# RBB_MCU7_V2_2_Connector.net
KiCad netlist of a schematic drawn in Altium Designer
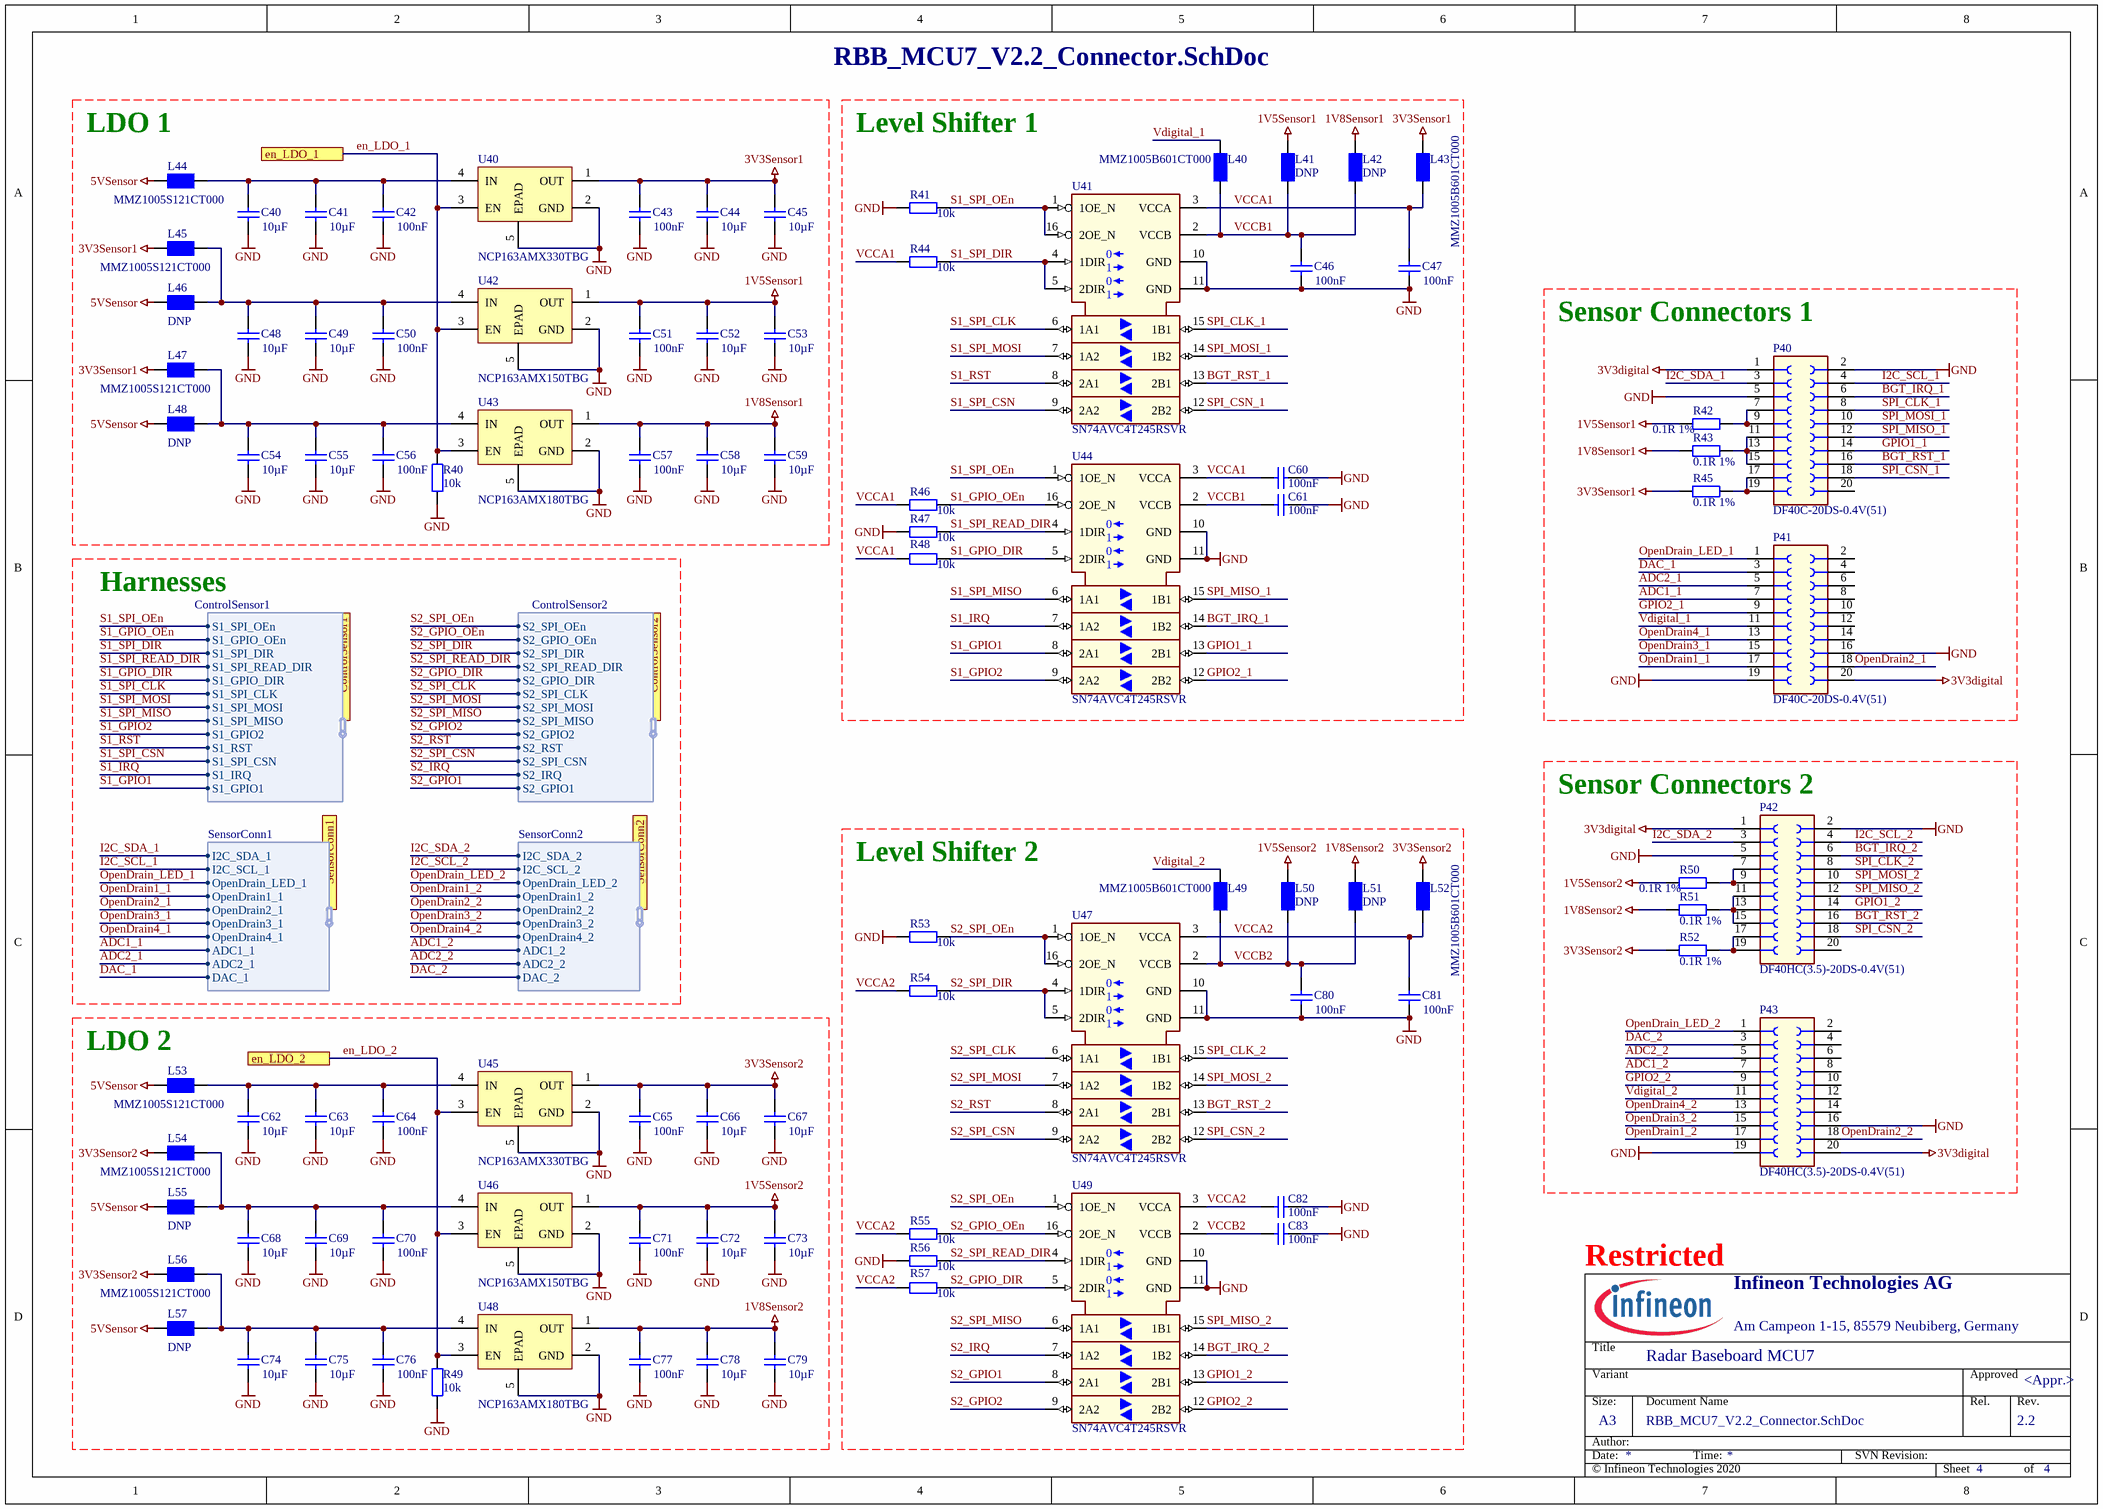
[diagram p0: RBB_MCU7_V2.2_Connector.SchDoc]

(export (version "E")
  (design (tool "Eeschema 10.0.6"))
  (components
    (comp (ref "C40")
      (value "10µF")
      (footprint "0402_C_Axon")
      (description "Capacitor")
      (fields (field (name "PUBLISHER") "Altium Limited"))
      (libsource (lib "Miscellaneous Devices") (part "Cap"))
    )
    (comp (ref "C41")
      (value "10µF")
      (footprint "0402_C_Axon")
      (description "Capacitor")
      (fields (field (name "PUBLISHER") "Altium Limited"))
      (libsource (lib "Miscellaneous Devices") (part "Cap"))
    )
    (comp (ref "C42")
      (value "100nF")
      (footprint "0402_C_Axon")
      (description "Capacitor")
      (fields (field (name "PUBLISHER") "Altium Limited"))
      (libsource (lib "Miscellaneous Devices") (part "Cap"))
    )
    (comp (ref "C43")
      (value "100nF")
      (footprint "0402_C_Axon")
      (description "Capacitor")
      (fields (field (name "PUBLISHER") "Altium Limited"))
      (libsource (lib "Miscellaneous Devices") (part "Cap"))
    )
    (comp (ref "C44")
      (value "10µF")
      (footprint "0402_C_Axon")
      (description "Capacitor")
      (fields (field (name "PUBLISHER") "Altium Limited"))
      (libsource (lib "Miscellaneous Devices") (part "Cap"))
    )
    (comp (ref "C45")
      (value "10µF")
      (footprint "0402_C_Axon")
      (description "Capacitor")
      (fields (field (name "PUBLISHER") "Altium Limited"))
      (libsource (lib "Miscellaneous Devices") (part "Cap"))
    )
    (comp (ref "C46")
      (value "100nF")
      (footprint "0402_C_Axon")
      (description "Capacitor")
      (fields (field (name "PUBLISHER") "Altium Limited"))
      (libsource (lib "Miscellaneous Devices") (part "Cap"))
    )
    (comp (ref "C47")
      (value "100nF")
      (footprint "0402_C_Axon")
      (description "Capacitor")
      (fields (field (name "PUBLISHER") "Altium Limited"))
      (libsource (lib "Miscellaneous Devices") (part "Cap"))
    )
    (comp (ref "C48")
      (value "10µF")
      (footprint "0402_C_Axon")
      (description "Capacitor")
      (fields (field (name "PUBLISHER") "Altium Limited"))
      (libsource (lib "Miscellaneous Devices") (part "Cap"))
    )
    (comp (ref "C49")
      (value "10µF")
      (footprint "0402_C_Axon")
      (description "Capacitor")
      (fields (field (name "PUBLISHER") "Altium Limited"))
      (libsource (lib "Miscellaneous Devices") (part "Cap"))
    )
    (comp (ref "C50")
      (value "100nF")
      (footprint "0402_C_Axon")
      (description "Capacitor")
      (fields (field (name "PUBLISHER") "Altium Limited"))
      (libsource (lib "Miscellaneous Devices") (part "Cap"))
    )
    (comp (ref "C51")
      (value "100nF")
      (footprint "0402_C_Axon")
      (description "Capacitor")
      (fields (field (name "PUBLISHER") "Altium Limited"))
      (libsource (lib "Miscellaneous Devices") (part "Cap"))
    )
    (comp (ref "C52")
      (value "10µF")
      (footprint "0402_C_Axon")
      (description "Capacitor")
      (fields (field (name "PUBLISHER") "Altium Limited"))
      (libsource (lib "Miscellaneous Devices") (part "Cap"))
    )
    (comp (ref "C53")
      (value "10µF")
      (footprint "0402_C_Axon")
      (description "Capacitor")
      (fields (field (name "PUBLISHER") "Altium Limited"))
      (libsource (lib "Miscellaneous Devices") (part "Cap"))
    )
    (comp (ref "C54")
      (value "10µF")
      (footprint "0402_C_Axon")
      (description "Capacitor")
      (fields (field (name "PUBLISHER") "Altium Limited"))
      (libsource (lib "Miscellaneous Devices") (part "Cap"))
    )
    (comp (ref "C55")
      (value "10µF")
      (footprint "0402_C_Axon")
      (description "Capacitor")
      (fields (field (name "PUBLISHER") "Altium Limited"))
      (libsource (lib "Miscellaneous Devices") (part "Cap"))
    )
    (comp (ref "C56")
      (value "100nF")
      (footprint "0402_C_Axon")
      (description "Capacitor")
      (fields (field (name "PUBLISHER") "Altium Limited"))
      (libsource (lib "Miscellaneous Devices") (part "Cap"))
    )
    (comp (ref "C57")
      (value "100nF")
      (footprint "0402_C_Axon")
      (description "Capacitor")
      (fields (field (name "PUBLISHER") "Altium Limited"))
      (libsource (lib "Miscellaneous Devices") (part "Cap"))
    )
    (comp (ref "C58")
      (value "10µF")
      (footprint "0402_C_Axon")
      (description "Capacitor")
      (fields (field (name "PUBLISHER") "Altium Limited"))
      (libsource (lib "Miscellaneous Devices") (part "Cap"))
    )
    (comp (ref "C59")
      (value "10µF")
      (footprint "0402_C_Axon")
      (description "Capacitor")
      (fields (field (name "PUBLISHER") "Altium Limited"))
      (libsource (lib "Miscellaneous Devices") (part "Cap"))
    )
    (comp (ref "C60")
      (value "100nF")
      (footprint "0402_C_Axon")
      (description "Capacitor")
      (fields (field (name "PUBLISHER") "Altium Limited"))
      (libsource (lib "Miscellaneous Devices") (part "Cap"))
    )
    (comp (ref "C61")
      (value "100nF")
      (footprint "0402_C_Axon")
      (description "Capacitor")
      (fields (field (name "PUBLISHER") "Altium Limited"))
      (libsource (lib "Miscellaneous Devices") (part "Cap"))
    )
    (comp (ref "C62")
      (value "10µF")
      (footprint "0402_C_Axon")
      (description "Capacitor")
      (fields (field (name "PUBLISHER") "Altium Limited"))
      (libsource (lib "Miscellaneous Devices") (part "Cap"))
    )
    (comp (ref "C63")
      (value "10µF")
      (footprint "0402_C_Axon")
      (description "Capacitor")
      (fields (field (name "PUBLISHER") "Altium Limited"))
      (libsource (lib "Miscellaneous Devices") (part "Cap"))
    )
    (comp (ref "C64")
      (value "100nF")
      (footprint "0402_C_Axon")
      (description "Capacitor")
      (fields (field (name "PUBLISHER") "Altium Limited"))
      (libsource (lib "Miscellaneous Devices") (part "Cap"))
    )
    (comp (ref "C65")
      (value "100nF")
      (footprint "0402_C_Axon")
      (description "Capacitor")
      (fields (field (name "PUBLISHER") "Altium Limited"))
      (libsource (lib "Miscellaneous Devices") (part "Cap"))
    )
    (comp (ref "C66")
      (value "10µF")
      (footprint "0402_C_Axon")
      (description "Capacitor")
      (fields (field (name "PUBLISHER") "Altium Limited"))
      (libsource (lib "Miscellaneous Devices") (part "Cap"))
    )
    (comp (ref "C67")
      (value "10µF")
      (footprint "0402_C_Axon")
      (description "Capacitor")
      (fields (field (name "PUBLISHER") "Altium Limited"))
      (libsource (lib "Miscellaneous Devices") (part "Cap"))
    )
    (comp (ref "C68")
      (value "10µF")
      (footprint "0402_C_Axon")
      (description "Capacitor")
      (fields (field (name "PUBLISHER") "Altium Limited"))
      (libsource (lib "Miscellaneous Devices") (part "Cap"))
    )
    (comp (ref "C69")
      (value "10µF")
      (footprint "0402_C_Axon")
      (description "Capacitor")
      (fields (field (name "PUBLISHER") "Altium Limited"))
      (libsource (lib "Miscellaneous Devices") (part "Cap"))
    )
    (comp (ref "C70")
      (value "100nF")
      (footprint "0402_C_Axon")
      (description "Capacitor")
      (fields (field (name "PUBLISHER") "Altium Limited"))
      (libsource (lib "Miscellaneous Devices") (part "Cap"))
    )
    (comp (ref "C71")
      (value "100nF")
      (footprint "0402_C_Axon")
      (description "Capacitor")
      (fields (field (name "PUBLISHER") "Altium Limited"))
      (libsource (lib "Miscellaneous Devices") (part "Cap"))
    )
    (comp (ref "C72")
      (value "10µF")
      (footprint "0402_C_Axon")
      (description "Capacitor")
      (fields (field (name "PUBLISHER") "Altium Limited"))
      (libsource (lib "Miscellaneous Devices") (part "Cap"))
    )
    (comp (ref "C73")
      (value "10µF")
      (footprint "0402_C_Axon")
      (description "Capacitor")
      (fields (field (name "PUBLISHER") "Altium Limited"))
      (libsource (lib "Miscellaneous Devices") (part "Cap"))
    )
    (comp (ref "C74")
      (value "10µF")
      (footprint "0402_C_Axon")
      (description "Capacitor")
      (fields (field (name "PUBLISHER") "Altium Limited"))
      (libsource (lib "Miscellaneous Devices") (part "Cap"))
    )
    (comp (ref "C75")
      (value "10µF")
      (footprint "0402_C_Axon")
      (description "Capacitor")
      (fields (field (name "PUBLISHER") "Altium Limited"))
      (libsource (lib "Miscellaneous Devices") (part "Cap"))
    )
    (comp (ref "C76")
      (value "100nF")
      (footprint "0402_C_Axon")
      (description "Capacitor")
      (fields (field (name "PUBLISHER") "Altium Limited"))
      (libsource (lib "Miscellaneous Devices") (part "Cap"))
    )
    (comp (ref "C77")
      (value "100nF")
      (footprint "0402_C_Axon")
      (description "Capacitor")
      (fields (field (name "PUBLISHER") "Altium Limited"))
      (libsource (lib "Miscellaneous Devices") (part "Cap"))
    )
    (comp (ref "C78")
      (value "10µF")
      (footprint "0402_C_Axon")
      (description "Capacitor")
      (fields (field (name "PUBLISHER") "Altium Limited"))
      (libsource (lib "Miscellaneous Devices") (part "Cap"))
    )
    (comp (ref "C79")
      (value "10µF")
      (footprint "0402_C_Axon")
      (description "Capacitor")
      (fields (field (name "PUBLISHER") "Altium Limited"))
      (libsource (lib "Miscellaneous Devices") (part "Cap"))
    )
    (comp (ref "C80")
      (value "100nF")
      (footprint "0402_C_Axon")
      (description "Capacitor")
      (fields (field (name "PUBLISHER") "Altium Limited"))
      (libsource (lib "Miscellaneous Devices") (part "Cap"))
    )
    (comp (ref "C81")
      (value "100nF")
      (footprint "0402_C_Axon")
      (description "Capacitor")
      (fields (field (name "PUBLISHER") "Altium Limited"))
      (libsource (lib "Miscellaneous Devices") (part "Cap"))
    )
    (comp (ref "C82")
      (value "100nF")
      (footprint "0402_C_Axon")
      (description "Capacitor")
      (fields (field (name "PUBLISHER") "Altium Limited"))
      (libsource (lib "Miscellaneous Devices") (part "Cap"))
    )
    (comp (ref "C83")
      (value "100nF")
      (footprint "0402_C_Axon")
      (description "Capacitor")
      (fields (field (name "PUBLISHER") "Altium Limited"))
      (libsource (lib "Miscellaneous Devices") (part "Cap"))
    )
    (comp (ref "L40")
      (value "MMZ1005B601CT000")
      (footprint "0402_L_Axon")
      (description "SMD Ferrite Bead")
      (libsource (lib "Tjuefire") (part "INDUCTOR1"))
    )
    (comp (ref "L41")
      (value "DNP")
      (footprint "0402_Empty_Axon")
      (description "SMD Ferrite Bead")
      (libsource (lib "Tjuefire") (part "INDUCTOR1"))
    )
    (comp (ref "L42")
      (value "DNP")
      (footprint "0402_Empty_Axon")
      (description "SMD Ferrite Bead")
      (libsource (lib "Tjuefire") (part "INDUCTOR1"))
    )
    (comp (ref "L43")
      (value "MMZ1005B601CT000")
      (footprint "0402_L_Axon")
      (description "SMD Ferrite Bead")
      (libsource (lib "Tjuefire") (part "INDUCTOR1"))
    )
    (comp (ref "L44")
      (value "MMZ1005S121CT000")
      (footprint "0402_L_Axon")
      (description "SMD Ferrite Bead")
      (libsource (lib "") (part "INDUCTOR1_1"))
    )
    (comp (ref "L45")
      (value "MMZ1005S121CT000")
      (footprint "0402_L_Axon")
      (description "SMD Ferrite Bead")
      (libsource (lib "") (part "INDUCTOR1_1"))
    )
    (comp (ref "L46")
      (value "DNP")
      (footprint "0402_Empty_Axon")
      (description "SMD Ferrite Bead")
      (libsource (lib "") (part "INDUCTOR1_1"))
    )
    (comp (ref "L47")
      (value "MMZ1005S121CT000")
      (footprint "0402_L_Axon")
      (description "SMD Ferrite Bead")
      (libsource (lib "") (part "INDUCTOR1_1"))
    )
    (comp (ref "L48")
      (value "DNP")
      (footprint "0402_Empty_Axon")
      (description "SMD Ferrite Bead")
      (libsource (lib "") (part "INDUCTOR1_1"))
    )
    (comp (ref "L49")
      (value "MMZ1005B601CT000")
      (footprint "0402_L_Axon")
      (description "SMD Ferrite Bead")
      (libsource (lib "Tjuefire") (part "INDUCTOR1"))
    )
    (comp (ref "L50")
      (value "DNP")
      (footprint "0402_Empty_Axon")
      (description "SMD Ferrite Bead")
      (libsource (lib "Tjuefire") (part "INDUCTOR1"))
    )
    (comp (ref "L51")
      (value "DNP")
      (footprint "0402_Empty_Axon")
      (description "SMD Ferrite Bead")
      (libsource (lib "Tjuefire") (part "INDUCTOR1"))
    )
    (comp (ref "L52")
      (value "MMZ1005B601CT000")
      (footprint "0402_L_Axon")
      (description "SMD Ferrite Bead")
      (libsource (lib "Tjuefire") (part "INDUCTOR1"))
    )
    (comp (ref "L53")
      (value "MMZ1005S121CT000")
      (footprint "0402_L_Axon")
      (description "SMD Ferrite Bead")
      (libsource (lib "") (part "INDUCTOR1_1"))
    )
    (comp (ref "L54")
      (value "MMZ1005S121CT000")
      (footprint "0402_L_Axon")
      (description "SMD Ferrite Bead")
      (libsource (lib "") (part "INDUCTOR1_1"))
    )
    (comp (ref "L55")
      (value "DNP")
      (footprint "0402_Empty_Axon")
      (description "SMD Ferrite Bead")
      (libsource (lib "") (part "INDUCTOR1_1"))
    )
    (comp (ref "L56")
      (value "MMZ1005S121CT000")
      (footprint "0402_L_Axon")
      (description "SMD Ferrite Bead")
      (libsource (lib "") (part "INDUCTOR1_1"))
    )
    (comp (ref "L57")
      (value "DNP")
      (footprint "0402_Empty_Axon")
      (description "SMD Ferrite Bead")
      (libsource (lib "") (part "INDUCTOR1_1"))
    )
    (comp (ref "P40")
      (value "DF40C-20DS-0.4V(51)")
      (footprint "Hatvan:CON-F-SMD-DF40C-20DS-0.4V(51)")
      (description "Board-to-FPC Connector, 0.4mm pitch, Female")
      (fields (field (name "MANUFACTURER") "Hirose Connectors"))
      (libsource (lib "PCBLibraryData") (part "Socket 10X2"))
    )
    (comp (ref "P41")
      (value "DF40C-20DS-0.4V(51)")
      (footprint "Hatvan:CON-F-SMD-DF40C-20DS-0.4V(51)")
      (description "Board-to-FPC Connector, 0.4mm pitch, Female")
      (fields (field (name "MANUFACTURER") "Hirose Connectors"))
      (libsource (lib "PCBLibraryData") (part "Socket 10X2"))
    )
    (comp (ref "P42")
      (value "DF40HC(3.5)-20DS-0.4V(51)")
      (footprint "Hatvan:CON-F-SMD-DF40C-20DS-0.4V(51)")
      (description "Board-to-FPC Connector, 0.4mm pitch, Female")
      (fields (field (name "MANUFACTURER") "Hirose Connectors"))
      (libsource (lib "PCBLibraryData") (part "Socket 10X2"))
    )
    (comp (ref "P43")
      (value "DF40HC(3.5)-20DS-0.4V(51)")
      (footprint "Hatvan:CON-F-SMD-DF40C-20DS-0.4V(51)")
      (description "Board-to-FPC Connector, 0.4mm pitch, Female")
      (fields (field (name "MANUFACTURER") "Hirose Connectors"))
      (libsource (lib "PCBLibraryData") (part "Socket 10X2"))
    )
    (comp (ref "R40")
      (value "10k")
      (footprint "0402_R_Axon")
      (description "Resistor")
      (libsource (lib "") (part "Res2_1"))
    )
    (comp (ref "R41")
      (value "10k")
      (footprint "0402_R_Axon")
      (description "Resistor")
      (libsource (lib "Miscellaneous Devices") (part "Res2"))
    )
    (comp (ref "R42")
      (value "0.1R 1%")
      (footprint "0603_R_Axon")
      (description "Resistor")
      (fields (field (name "PUBLISHER") "Altium Limited"))
      (libsource (lib "") (part "Res2_2"))
    )
    (comp (ref "R43")
      (value "0.1R 1%")
      (footprint "0603_R_Axon")
      (description "Resistor")
      (fields (field (name "PUBLISHER") "Altium Limited"))
      (libsource (lib "") (part "Res2_2"))
    )
    (comp (ref "R44")
      (value "10k")
      (footprint "0402_R_Axon")
      (description "Resistor")
      (libsource (lib "Miscellaneous Devices") (part "Res2"))
    )
    (comp (ref "R45")
      (value "0.1R 1%")
      (footprint "0603_R_Axon")
      (description "Resistor")
      (fields (field (name "PUBLISHER") "Altium Limited"))
      (libsource (lib "") (part "Res2_2"))
    )
    (comp (ref "R46")
      (value "10k")
      (footprint "0402_R_Axon")
      (description "Resistor")
      (libsource (lib "Miscellaneous Devices") (part "Res2"))
    )
    (comp (ref "R47")
      (value "10k")
      (footprint "0402_R_Axon")
      (description "Resistor")
      (libsource (lib "Miscellaneous Devices") (part "Res2"))
    )
    (comp (ref "R48")
      (value "10k")
      (footprint "0402_R_Axon")
      (description "Resistor")
      (libsource (lib "Miscellaneous Devices") (part "Res2"))
    )
    (comp (ref "R49")
      (value "10k")
      (footprint "0402_R_Axon")
      (description "Resistor")
      (libsource (lib "") (part "Res2_1"))
    )
    (comp (ref "R50")
      (value "0.1R 1%")
      (footprint "0603_R_Axon")
      (description "Resistor")
      (fields (field (name "PUBLISHER") "Altium Limited"))
      (libsource (lib "") (part "Res2_3"))
    )
    (comp (ref "R51")
      (value "0.1R 1%")
      (footprint "0603_R_Axon")
      (description "Resistor")
      (fields (field (name "PUBLISHER") "Altium Limited"))
      (libsource (lib "") (part "Res2_3"))
    )
    (comp (ref "R52")
      (value "0.1R 1%")
      (footprint "0603_R_Axon")
      (description "Resistor")
      (fields (field (name "PUBLISHER") "Altium Limited"))
      (libsource (lib "") (part "Res2_3"))
    )
    (comp (ref "R53")
      (value "10k")
      (footprint "0402_R_Axon")
      (description "Resistor")
      (libsource (lib "Miscellaneous Devices") (part "Res2"))
    )
    (comp (ref "R54")
      (value "10k")
      (footprint "0402_R_Axon")
      (description "Resistor")
      (libsource (lib "Miscellaneous Devices") (part "Res2"))
    )
    (comp (ref "R55")
      (value "10k")
      (footprint "0402_R_Axon")
      (description "Resistor")
      (libsource (lib "Miscellaneous Devices") (part "Res2"))
    )
    (comp (ref "R56")
      (value "10k")
      (footprint "0402_R_Axon")
      (description "Resistor")
      (libsource (lib "Miscellaneous Devices") (part "Res2"))
    )
    (comp (ref "R57")
      (value "10k")
      (footprint "0402_R_Axon")
      (description "Resistor")
      (libsource (lib "Miscellaneous Devices") (part "Res2"))
    )
    (comp (ref "U40")
      (value "NCP163AMX330TBG")
      (footprint "NCP163")
      (description "NCP163 - LDO 250mA, XDFN4,\r\nultra-low noise, high PSRR")
      (libsource (lib "Hatvan") (part "NCP177"))
    )
    (comp (ref "U41")
      (value "SN74AVC4T245RSVR")
      (footprint "SN74AVC4T245RSVR-Hatvan")
      (description "Dual-Bit Bus Transceiver with Configurable Voltage Translation and 3-State Output")
      (fields
        (field (name "LEGACY PARTNUMBER") "IC02601282")
        (field (name "MANUFACTURER") "Texas Instruments")
        (field (name "MANUFACTURER ORDER NUMBER") "SN74AVC4T245RSVR")
      )
      (libsource (lib "PCBLibraryData") (part "SN74AVC4T245RSVR"))
    )
    (comp (ref "U42")
      (value "NCP163AMX150TBG")
      (footprint "NCP163")
      (description "NCP163 - LDO 250mA, XDFN4,\r\nultra-low noise, high PSRR")
      (libsource (lib "Hatvan") (part "NCP177"))
    )
    (comp (ref "U43")
      (value "NCP163AMX180TBG")
      (footprint "NCP163")
      (description "NCP163 - LDO 250mA, XDFN4,\r\nultra-low noise, high PSRR")
      (libsource (lib "Hatvan") (part "NCP177"))
    )
    (comp (ref "U44")
      (value "SN74AVC4T245RSVR")
      (footprint "SN74AVC4T245RSVR-Hatvan")
      (description "Dual-Bit Bus Transceiver with Configurable Voltage Translation and 3-State Output")
      (fields
        (field (name "LEGACY PARTNUMBER") "IC02601282")
        (field (name "MANUFACTURER") "Texas Instruments")
        (field (name "MANUFACTURER ORDER NUMBER") "SN74AVC4T245RSVR")
      )
      (libsource (lib "PCBLibraryData") (part "SN74AVC4T245RSVR"))
    )
    (comp (ref "U45")
      (value "NCP163AMX330TBG")
      (footprint "NCP163")
      (description "NCP163 - LDO 250mA, XDFN4,\r\nultra-low noise, high PSRR")
      (libsource (lib "Hatvan") (part "NCP177"))
    )
    (comp (ref "U46")
      (value "NCP163AMX150TBG")
      (footprint "NCP163")
      (description "NCP163 - LDO 250mA, XDFN4,\r\nultra-low noise, high PSRR")
      (libsource (lib "Hatvan") (part "NCP177"))
    )
    (comp (ref "U47")
      (value "SN74AVC4T245RSVR")
      (footprint "SN74AVC4T245RSVR-Hatvan")
      (description "Dual-Bit Bus Transceiver with Configurable Voltage Translation and 3-State Output")
      (fields
        (field (name "LEGACY PARTNUMBER") "IC02601282")
        (field (name "MANUFACTURER") "Texas Instruments")
        (field (name "MANUFACTURER ORDER NUMBER") "SN74AVC4T245RSVR")
      )
      (libsource (lib "PCBLibraryData") (part "SN74AVC4T245RSVR"))
    )
    (comp (ref "U48")
      (value "NCP163AMX180TBG")
      (footprint "NCP163")
      (description "NCP163 - LDO 250mA, XDFN4,\r\nultra-low noise, high PSRR")
      (libsource (lib "Hatvan") (part "NCP177"))
    )
    (comp (ref "U49")
      (value "SN74AVC4T245RSVR")
      (footprint "SN74AVC4T245RSVR-Hatvan")
      (description "Dual-Bit Bus Transceiver with Configurable Voltage Translation and 3-State Output")
      (fields
        (field (name "LEGACY PARTNUMBER") "IC02601282")
        (field (name "MANUFACTURER") "Texas Instruments")
        (field (name "MANUFACTURER ORDER NUMBER") "SN74AVC4T245RSVR")
      )
      (libsource (lib "PCBLibraryData") (part "SN74AVC4T245RSVR"))
    )
  )
  (nets
    (net (code "5") (name "/ADC1_1") (class "Default")
      (node (ref "P41") (pin "7") (pinfunction "7_7") (pintype "passive"))
    )
    (net (code "6") (name "/ADC1_2") (class "Default")
      (node (ref "P43") (pin "7") (pinfunction "7_7") (pintype "passive"))
    )
    (net (code "7") (name "/ADC2_1") (class "Default")
      (node (ref "P41") (pin "5") (pinfunction "5_5") (pintype "passive"))
    )
    (net (code "8") (name "/ADC2_2") (class "Default")
      (node (ref "P43") (pin "5") (pinfunction "5_5") (pintype "passive"))
    )
    (net (code "9") (name "/BGT_IRQ_1") (class "Default")
      (node (ref "P40") (pin "6") (pinfunction "6_6") (pintype "passive"))
      (node (ref "U44") (pin "14") (pinfunction "1B2_14") (pintype "bidirectional"))
    )
    (net (code "10") (name "/BGT_IRQ_2") (class "Default")
      (node (ref "P42") (pin "6") (pinfunction "6_6") (pintype "passive"))
      (node (ref "U49") (pin "14") (pinfunction "1B2_14") (pintype "bidirectional"))
    )
    (net (code "11") (name "/BGT_RST_1") (class "Default")
      (node (ref "P40") (pin "16") (pinfunction "16_16") (pintype "passive"))
      (node (ref "U41") (pin "13") (pinfunction "2B1_13") (pintype "bidirectional"))
    )
    (net (code "12") (name "/BGT_RST_2") (class "Default")
      (node (ref "P42") (pin "16") (pinfunction "16_16") (pintype "passive"))
      (node (ref "U47") (pin "13") (pinfunction "2B1_13") (pintype "bidirectional"))
    )
    (net (code "13") (name "/DAC_1") (class "Default")
      (node (ref "P41") (pin "3") (pinfunction "3_3") (pintype "passive"))
    )
    (net (code "14") (name "/DAC_2") (class "Default")
      (node (ref "P43") (pin "3") (pinfunction "3_3") (pintype "passive"))
    )
    (net (code "15") (name "/GPIO1_1") (class "Default")
      (node (ref "P40") (pin "14") (pinfunction "14_14") (pintype "passive"))
      (node (ref "U44") (pin "13") (pinfunction "2B1_13") (pintype "bidirectional"))
    )
    (net (code "16") (name "/GPIO1_2") (class "Default")
      (node (ref "P42") (pin "14") (pinfunction "14_14") (pintype "passive"))
      (node (ref "U49") (pin "13") (pinfunction "2B1_13") (pintype "bidirectional"))
    )
    (net (code "17") (name "/GPIO2_1") (class "Default")
      (node (ref "P41") (pin "9") (pinfunction "9_9") (pintype "passive"))
      (node (ref "U44") (pin "12") (pinfunction "2B2_12") (pintype "bidirectional"))
    )
    (net (code "18") (name "/GPIO2_2") (class "Default")
      (node (ref "P43") (pin "9") (pinfunction "9_9") (pintype "passive"))
      (node (ref "U49") (pin "12") (pinfunction "2B2_12") (pintype "bidirectional"))
    )
    (net (code "19") (name "/I2C_SCL_1") (class "Default")
      (node (ref "P40") (pin "4") (pinfunction "4_4") (pintype "passive"))
    )
    (net (code "20") (name "/I2C_SCL_2") (class "Default")
      (node (ref "P42") (pin "4") (pinfunction "4_4") (pintype "passive"))
    )
    (net (code "21") (name "/I2C_SDA_1") (class "Default")
      (node (ref "P40") (pin "3") (pinfunction "3_3") (pintype "passive"))
    )
    (net (code "22") (name "/I2C_SDA_2") (class "Default")
      (node (ref "P42") (pin "3") (pinfunction "3_3") (pintype "passive"))
    )
    (net (code "23") (name "/OpenDrain1_1") (class "Default")
      (node (ref "P41") (pin "17") (pinfunction "17_17") (pintype "passive"))
    )
    (net (code "24") (name "/OpenDrain1_2") (class "Default")
      (node (ref "P43") (pin "17") (pinfunction "17_17") (pintype "passive"))
    )
    (net (code "25") (name "/OpenDrain2_1") (class "Default")
      (node (ref "P41") (pin "18") (pinfunction "18_18") (pintype "passive"))
    )
    (net (code "26") (name "/OpenDrain2_2") (class "Default")
      (node (ref "P43") (pin "18") (pinfunction "18_18") (pintype "passive"))
    )
    (net (code "27") (name "/OpenDrain3_1") (class "Default")
      (node (ref "P41") (pin "15") (pinfunction "15_15") (pintype "passive"))
    )
    (net (code "28") (name "/OpenDrain3_2") (class "Default")
      (node (ref "P43") (pin "15") (pinfunction "15_15") (pintype "passive"))
    )
    (net (code "29") (name "/OpenDrain4_1") (class "Default")
      (node (ref "P41") (pin "13") (pinfunction "13_13") (pintype "passive"))
    )
    (net (code "30") (name "/OpenDrain4_2") (class "Default")
      (node (ref "P43") (pin "13") (pinfunction "13_13") (pintype "passive"))
    )
    (net (code "31") (name "/OpenDrain_LED_1") (class "Default")
      (node (ref "P41") (pin "1") (pinfunction "1_1") (pintype "passive"))
    )
    (net (code "32") (name "/OpenDrain_LED_2") (class "Default")
      (node (ref "P43") (pin "1") (pinfunction "1_1") (pintype "passive"))
    )
    (net (code "33") (name "/S1_GPIO1") (class "Default")
      (node (ref "U44") (pin "8") (pinfunction "2A1_8") (pintype "bidirectional"))
    )
    (net (code "34") (name "/S1_GPIO2") (class "Default")
      (node (ref "U44") (pin "9") (pinfunction "2A2_9") (pintype "bidirectional"))
    )
    (net (code "35") (name "/S1_GPIO_DIR") (class "Default")
      (node (ref "R48") (pin "2") (pinfunction "2_2") (pintype "passive"))
      (node (ref "U44") (pin "5") (pinfunction "2DIR_5") (pintype "input"))
    )
    (net (code "36") (name "/S1_GPIO_OEn") (class "Default")
      (node (ref "R46") (pin "2") (pinfunction "2_2") (pintype "passive"))
      (node (ref "U44") (pin "16") (pinfunction "2OE_N_16") (pintype "input"))
    )
    (net (code "37") (name "/S1_IRQ") (class "Default")
      (node (ref "U44") (pin "7") (pinfunction "1A2_7") (pintype "bidirectional"))
    )
    (net (code "38") (name "/S1_RST") (class "Default")
      (node (ref "U41") (pin "8") (pinfunction "2A1_8") (pintype "bidirectional"))
    )
    (net (code "39") (name "/S1_SPI_CLK") (class "Default")
      (node (ref "U41") (pin "6") (pinfunction "1A1_6") (pintype "bidirectional"))
    )
    (net (code "40") (name "/S1_SPI_CSN") (class "Default")
      (node (ref "U41") (pin "9") (pinfunction "2A2_9") (pintype "bidirectional"))
    )
    (net (code "41") (name "/S1_SPI_DIR") (class "Default")
      (node (ref "R44") (pin "2") (pinfunction "2_2") (pintype "passive"))
      (node (ref "U41") (pin "4") (pinfunction "1DIR_4") (pintype "input"))
      (node (ref "U41") (pin "5") (pinfunction "2DIR_5") (pintype "input"))
    )
    (net (code "42") (name "/S1_SPI_MISO") (class "Default")
      (node (ref "U44") (pin "6") (pinfunction "1A1_6") (pintype "bidirectional"))
    )
    (net (code "43") (name "/S1_SPI_MOSI") (class "Default")
      (node (ref "U41") (pin "7") (pinfunction "1A2_7") (pintype "bidirectional"))
    )
    (net (code "44") (name "/S1_SPI_OEn") (class "Default")
      (node (ref "R41") (pin "2") (pinfunction "2_2") (pintype "passive"))
      (node (ref "U41") (pin "1") (pinfunction "1OE_N_1") (pintype "input"))
      (node (ref "U41") (pin "16") (pinfunction "2OE_N_16") (pintype "input"))
      (node (ref "U44") (pin "1") (pinfunction "1OE_N_1") (pintype "input"))
    )
    (net (code "45") (name "/S1_SPI_READ_DIR") (class "Default")
      (node (ref "R47") (pin "2") (pinfunction "2_2") (pintype "passive"))
      (node (ref "U44") (pin "4") (pinfunction "1DIR_4") (pintype "input"))
    )
    (net (code "46") (name "/S2_GPIO1") (class "Default")
      (node (ref "U49") (pin "8") (pinfunction "2A1_8") (pintype "bidirectional"))
    )
    (net (code "47") (name "/S2_GPIO2") (class "Default")
      (node (ref "U49") (pin "9") (pinfunction "2A2_9") (pintype "bidirectional"))
    )
    (net (code "48") (name "/S2_GPIO_DIR") (class "Default")
      (node (ref "R57") (pin "2") (pinfunction "2_2") (pintype "passive"))
      (node (ref "U49") (pin "5") (pinfunction "2DIR_5") (pintype "input"))
    )
    (net (code "49") (name "/S2_GPIO_OEn") (class "Default")
      (node (ref "R55") (pin "2") (pinfunction "2_2") (pintype "passive"))
      (node (ref "U49") (pin "16") (pinfunction "2OE_N_16") (pintype "input"))
    )
    (net (code "50") (name "/S2_IRQ") (class "Default")
      (node (ref "U49") (pin "7") (pinfunction "1A2_7") (pintype "bidirectional"))
    )
    (net (code "51") (name "/S2_RST") (class "Default")
      (node (ref "U47") (pin "8") (pinfunction "2A1_8") (pintype "bidirectional"))
    )
    (net (code "52") (name "/S2_SPI_CLK") (class "Default")
      (node (ref "U47") (pin "6") (pinfunction "1A1_6") (pintype "bidirectional"))
    )
    (net (code "53") (name "/S2_SPI_CSN") (class "Default")
      (node (ref "U47") (pin "9") (pinfunction "2A2_9") (pintype "bidirectional"))
    )
    (net (code "54") (name "/S2_SPI_DIR") (class "Default")
      (node (ref "R54") (pin "2") (pinfunction "2_2") (pintype "passive"))
      (node (ref "U47") (pin "4") (pinfunction "1DIR_4") (pintype "input"))
      (node (ref "U47") (pin "5") (pinfunction "2DIR_5") (pintype "input"))
    )
    (net (code "55") (name "/S2_SPI_MISO") (class "Default")
      (node (ref "U49") (pin "6") (pinfunction "1A1_6") (pintype "bidirectional"))
    )
    (net (code "56") (name "/S2_SPI_MOSI") (class "Default")
      (node (ref "U47") (pin "7") (pinfunction "1A2_7") (pintype "bidirectional"))
    )
    (net (code "57") (name "/S2_SPI_OEn") (class "Default")
      (node (ref "R53") (pin "2") (pinfunction "2_2") (pintype "passive"))
      (node (ref "U47") (pin "1") (pinfunction "1OE_N_1") (pintype "input"))
      (node (ref "U47") (pin "16") (pinfunction "2OE_N_16") (pintype "input"))
      (node (ref "U49") (pin "1") (pinfunction "1OE_N_1") (pintype "input"))
    )
    (net (code "58") (name "/S2_SPI_READ_DIR") (class "Default")
      (node (ref "R56") (pin "2") (pinfunction "2_2") (pintype "passive"))
      (node (ref "U49") (pin "4") (pinfunction "1DIR_4") (pintype "input"))
    )
    (net (code "59") (name "/SPI_CLK_1") (class "Default")
      (node (ref "P40") (pin "8") (pinfunction "8_8") (pintype "passive"))
      (node (ref "U41") (pin "15") (pinfunction "1B1_15") (pintype "bidirectional"))
    )
    (net (code "60") (name "/SPI_CLK_2") (class "Default")
      (node (ref "P42") (pin "8") (pinfunction "8_8") (pintype "passive"))
      (node (ref "U47") (pin "15") (pinfunction "1B1_15") (pintype "bidirectional"))
    )
    (net (code "61") (name "/SPI_CSN_1") (class "Default")
      (node (ref "P40") (pin "18") (pinfunction "18_18") (pintype "passive"))
      (node (ref "U41") (pin "12") (pinfunction "2B2_12") (pintype "bidirectional"))
    )
    (net (code "62") (name "/SPI_CSN_2") (class "Default")
      (node (ref "P42") (pin "18") (pinfunction "18_18") (pintype "passive"))
      (node (ref "U47") (pin "12") (pinfunction "2B2_12") (pintype "bidirectional"))
    )
    (net (code "63") (name "/SPI_MISO_1") (class "Default")
      (node (ref "P40") (pin "12") (pinfunction "12_12") (pintype "passive"))
      (node (ref "U44") (pin "15") (pinfunction "1B1_15") (pintype "bidirectional"))
    )
    (net (code "64") (name "/SPI_MISO_2") (class "Default")
      (node (ref "P42") (pin "12") (pinfunction "12_12") (pintype "passive"))
      (node (ref "U49") (pin "15") (pinfunction "1B1_15") (pintype "bidirectional"))
    )
    (net (code "65") (name "/SPI_MOSI_1") (class "Default")
      (node (ref "P40") (pin "10") (pinfunction "10_10") (pintype "passive"))
      (node (ref "U41") (pin "14") (pinfunction "1B2_14") (pintype "bidirectional"))
    )
    (net (code "66") (name "/SPI_MOSI_2") (class "Default")
      (node (ref "P42") (pin "10") (pinfunction "10_10") (pintype "passive"))
      (node (ref "U47") (pin "14") (pinfunction "1B2_14") (pintype "bidirectional"))
    )
    (net (code "67") (name "/VCCA1") (class "Default")
      (node (ref "C47") (pin "2") (pinfunction "2_2") (pintype "passive"))
      (node (ref "C60") (pin "2") (pinfunction "2_2") (pintype "passive"))
      (node (ref "L43") (pin "1") (pinfunction "1_1") (pintype "passive"))
      (node (ref "R44") (pin "1") (pinfunction "1_1") (pintype "passive"))
      (node (ref "R46") (pin "1") (pinfunction "1_1") (pintype "passive"))
      (node (ref "R48") (pin "1") (pinfunction "1_1") (pintype "passive"))
      (node (ref "U41") (pin "3") (pinfunction "VCCA_3") (pintype "power_in"))
      (node (ref "U44") (pin "3") (pinfunction "VCCA_3") (pintype "power_in"))
    )
    (net (code "68") (name "/VCCA2") (class "Default")
      (node (ref "C81") (pin "2") (pinfunction "2_2") (pintype "passive"))
      (node (ref "C82") (pin "2") (pinfunction "2_2") (pintype "passive"))
      (node (ref "L52") (pin "1") (pinfunction "1_1") (pintype "passive"))
      (node (ref "R54") (pin "1") (pinfunction "1_1") (pintype "passive"))
      (node (ref "R55") (pin "1") (pinfunction "1_1") (pintype "passive"))
      (node (ref "R57") (pin "1") (pinfunction "1_1") (pintype "passive"))
      (node (ref "U47") (pin "3") (pinfunction "VCCA_3") (pintype "power_in"))
      (node (ref "U49") (pin "3") (pinfunction "VCCA_3") (pintype "power_in"))
    )
    (net (code "69") (name "/VCCB1") (class "Default")
      (node (ref "C46") (pin "2") (pinfunction "2_2") (pintype "passive"))
      (node (ref "C61") (pin "2") (pinfunction "2_2") (pintype "passive"))
      (node (ref "L40") (pin "1") (pinfunction "1_1") (pintype "passive"))
      (node (ref "L41") (pin "1") (pinfunction "1_1") (pintype "passive"))
      (node (ref "L42") (pin "1") (pinfunction "1_1") (pintype "passive"))
      (node (ref "U41") (pin "2") (pinfunction "VCCB_2") (pintype "power_in"))
      (node (ref "U44") (pin "2") (pinfunction "VCCB_2") (pintype "power_in"))
    )
    (net (code "70") (name "/VCCB2") (class "Default")
      (node (ref "C80") (pin "2") (pinfunction "2_2") (pintype "passive"))
      (node (ref "C83") (pin "2") (pinfunction "2_2") (pintype "passive"))
      (node (ref "L49") (pin "1") (pinfunction "1_1") (pintype "passive"))
      (node (ref "L50") (pin "1") (pinfunction "1_1") (pintype "passive"))
      (node (ref "L51") (pin "1") (pinfunction "1_1") (pintype "passive"))
      (node (ref "U47") (pin "2") (pinfunction "VCCB_2") (pintype "power_in"))
      (node (ref "U49") (pin "2") (pinfunction "VCCB_2") (pintype "power_in"))
    )
    (net (code "71") (name "/Vdigital_1") (class "Default")
      (node (ref "L40") (pin "2") (pinfunction "2_2") (pintype "passive"))
      (node (ref "P41") (pin "11") (pinfunction "11_11") (pintype "passive"))
    )
    (net (code "72") (name "/Vdigital_2") (class "Default")
      (node (ref "L49") (pin "2") (pinfunction "2_2") (pintype "passive"))
      (node (ref "P43") (pin "11") (pinfunction "11_11") (pintype "passive"))
    )
    (net (code "73") (name "/en_LDO_1") (class "Default")
      (node (ref "R40") (pin "1") (pinfunction "1_1") (pintype "passive"))
      (node (ref "U40") (pin "3") (pinfunction "EN_3") (pintype "passive"))
      (node (ref "U42") (pin "3") (pinfunction "EN_3") (pintype "passive"))
      (node (ref "U43") (pin "3") (pinfunction "EN_3") (pintype "passive"))
    )
    (net (code "74") (name "/en_LDO_2") (class "Default")
      (node (ref "R49") (pin "1") (pinfunction "1_1") (pintype "passive"))
      (node (ref "U45") (pin "3") (pinfunction "EN_3") (pintype "passive"))
      (node (ref "U46") (pin "3") (pinfunction "EN_3") (pintype "passive"))
      (node (ref "U48") (pin "3") (pinfunction "EN_3") (pintype "passive"))
    )
    (net (code "79") (name "1V5Sensor1") (class "Default")
      (node (ref "C51") (pin "2") (pinfunction "2_2") (pintype "passive"))
      (node (ref "C52") (pin "2") (pinfunction "2_2") (pintype "passive"))
      (node (ref "C53") (pin "2") (pinfunction "2_2") (pintype "passive"))
      (node (ref "L41") (pin "2") (pinfunction "2_2") (pintype "passive"))
      (node (ref "R42") (pin "2") (pinfunction "2_2") (pintype "passive"))
      (node (ref "U42") (pin "1") (pinfunction "OUT_1") (pintype "passive"))
    )
    (net (code "80") (name "1V5Sensor2") (class "Default")
      (node (ref "C71") (pin "2") (pinfunction "2_2") (pintype "passive"))
      (node (ref "C72") (pin "2") (pinfunction "2_2") (pintype "passive"))
      (node (ref "C73") (pin "2") (pinfunction "2_2") (pintype "passive"))
      (node (ref "L50") (pin "2") (pinfunction "2_2") (pintype "passive"))
      (node (ref "R50") (pin "2") (pinfunction "2_2") (pintype "passive"))
      (node (ref "U46") (pin "1") (pinfunction "OUT_1") (pintype "passive"))
    )
    (net (code "81") (name "1V8Sensor1") (class "Default")
      (node (ref "C57") (pin "2") (pinfunction "2_2") (pintype "passive"))
      (node (ref "C58") (pin "2") (pinfunction "2_2") (pintype "passive"))
      (node (ref "C59") (pin "2") (pinfunction "2_2") (pintype "passive"))
      (node (ref "L42") (pin "2") (pinfunction "2_2") (pintype "passive"))
      (node (ref "R43") (pin "2") (pinfunction "2_2") (pintype "passive"))
      (node (ref "U43") (pin "1") (pinfunction "OUT_1") (pintype "passive"))
    )
    (net (code "82") (name "1V8Sensor2") (class "Default")
      (node (ref "C77") (pin "2") (pinfunction "2_2") (pintype "passive"))
      (node (ref "C78") (pin "2") (pinfunction "2_2") (pintype "passive"))
      (node (ref "C79") (pin "2") (pinfunction "2_2") (pintype "passive"))
      (node (ref "L51") (pin "2") (pinfunction "2_2") (pintype "passive"))
      (node (ref "R51") (pin "2") (pinfunction "2_2") (pintype "passive"))
      (node (ref "U48") (pin "1") (pinfunction "OUT_1") (pintype "passive"))
    )
    (net (code "83") (name "3V3Sensor1") (class "Default")
      (node (ref "C43") (pin "2") (pinfunction "2_2") (pintype "passive"))
      (node (ref "C44") (pin "2") (pinfunction "2_2") (pintype "passive"))
      (node (ref "C45") (pin "2") (pinfunction "2_2") (pintype "passive"))
      (node (ref "L43") (pin "2") (pinfunction "2_2") (pintype "passive"))
      (node (ref "L45") (pin "1") (pinfunction "1_1") (pintype "passive"))
      (node (ref "L47") (pin "1") (pinfunction "1_1") (pintype "passive"))
      (node (ref "R45") (pin "2") (pinfunction "2_2") (pintype "passive"))
      (node (ref "U40") (pin "1") (pinfunction "OUT_1") (pintype "passive"))
    )
    (net (code "84") (name "3V3Sensor2") (class "Default")
      (node (ref "C65") (pin "2") (pinfunction "2_2") (pintype "passive"))
      (node (ref "C66") (pin "2") (pinfunction "2_2") (pintype "passive"))
      (node (ref "C67") (pin "2") (pinfunction "2_2") (pintype "passive"))
      (node (ref "L52") (pin "2") (pinfunction "2_2") (pintype "passive"))
      (node (ref "L54") (pin "1") (pinfunction "1_1") (pintype "passive"))
      (node (ref "L56") (pin "1") (pinfunction "1_1") (pintype "passive"))
      (node (ref "R52") (pin "2") (pinfunction "2_2") (pintype "passive"))
      (node (ref "U45") (pin "1") (pinfunction "OUT_1") (pintype "passive"))
    )
    (net (code "85") (name "3V3digital") (class "Default")
      (node (ref "P40") (pin "1") (pinfunction "1_1") (pintype "passive"))
      (node (ref "P41") (pin "20") (pinfunction "20_20") (pintype "passive"))
      (node (ref "P42") (pin "1") (pinfunction "1_1") (pintype "passive"))
      (node (ref "P43") (pin "20") (pinfunction "20_20") (pintype "passive"))
    )
    (net (code "86") (name "5VSensor") (class "Default")
      (node (ref "L44") (pin "1") (pinfunction "1_1") (pintype "passive"))
      (node (ref "L46") (pin "1") (pinfunction "1_1") (pintype "passive"))
      (node (ref "L48") (pin "1") (pinfunction "1_1") (pintype "passive"))
      (node (ref "L53") (pin "1") (pinfunction "1_1") (pintype "passive"))
      (node (ref "L55") (pin "1") (pinfunction "1_1") (pintype "passive"))
      (node (ref "L57") (pin "1") (pinfunction "1_1") (pintype "passive"))
    )
    (net (code "87") (name "GND") (class "Default")
      (node (ref "C40") (pin "1") (pinfunction "1_1") (pintype "passive"))
      (node (ref "C41") (pin "1") (pinfunction "1_1") (pintype "passive"))
      (node (ref "C42") (pin "1") (pinfunction "1_1") (pintype "passive"))
      (node (ref "C43") (pin "1") (pinfunction "1_1") (pintype "passive"))
      (node (ref "C44") (pin "1") (pinfunction "1_1") (pintype "passive"))
      (node (ref "C45") (pin "1") (pinfunction "1_1") (pintype "passive"))
      (node (ref "C46") (pin "1") (pinfunction "1_1") (pintype "passive"))
      (node (ref "C47") (pin "1") (pinfunction "1_1") (pintype "passive"))
      (node (ref "C48") (pin "1") (pinfunction "1_1") (pintype "passive"))
      (node (ref "C49") (pin "1") (pinfunction "1_1") (pintype "passive"))
      (node (ref "C50") (pin "1") (pinfunction "1_1") (pintype "passive"))
      (node (ref "C51") (pin "1") (pinfunction "1_1") (pintype "passive"))
      (node (ref "C52") (pin "1") (pinfunction "1_1") (pintype "passive"))
      (node (ref "C53") (pin "1") (pinfunction "1_1") (pintype "passive"))
      (node (ref "C54") (pin "1") (pinfunction "1_1") (pintype "passive"))
      (node (ref "C55") (pin "1") (pinfunction "1_1") (pintype "passive"))
      (node (ref "C56") (pin "1") (pinfunction "1_1") (pintype "passive"))
      (node (ref "C57") (pin "1") (pinfunction "1_1") (pintype "passive"))
      (node (ref "C58") (pin "1") (pinfunction "1_1") (pintype "passive"))
      (node (ref "C59") (pin "1") (pinfunction "1_1") (pintype "passive"))
      (node (ref "C60") (pin "1") (pinfunction "1_1") (pintype "passive"))
      (node (ref "C61") (pin "1") (pinfunction "1_1") (pintype "passive"))
      (node (ref "C62") (pin "1") (pinfunction "1_1") (pintype "passive"))
      (node (ref "C63") (pin "1") (pinfunction "1_1") (pintype "passive"))
      (node (ref "C64") (pin "1") (pinfunction "1_1") (pintype "passive"))
      (node (ref "C65") (pin "1") (pinfunction "1_1") (pintype "passive"))
      (node (ref "C66") (pin "1") (pinfunction "1_1") (pintype "passive"))
      (node (ref "C67") (pin "1") (pinfunction "1_1") (pintype "passive"))
      (node (ref "C68") (pin "1") (pinfunction "1_1") (pintype "passive"))
      (node (ref "C69") (pin "1") (pinfunction "1_1") (pintype "passive"))
      (node (ref "C70") (pin "1") (pinfunction "1_1") (pintype "passive"))
      (node (ref "C71") (pin "1") (pinfunction "1_1") (pintype "passive"))
      (node (ref "C72") (pin "1") (pinfunction "1_1") (pintype "passive"))
      (node (ref "C73") (pin "1") (pinfunction "1_1") (pintype "passive"))
      (node (ref "C74") (pin "1") (pinfunction "1_1") (pintype "passive"))
      (node (ref "C75") (pin "1") (pinfunction "1_1") (pintype "passive"))
      (node (ref "C76") (pin "1") (pinfunction "1_1") (pintype "passive"))
      (node (ref "C77") (pin "1") (pinfunction "1_1") (pintype "passive"))
      (node (ref "C78") (pin "1") (pinfunction "1_1") (pintype "passive"))
      (node (ref "C79") (pin "1") (pinfunction "1_1") (pintype "passive"))
      (node (ref "C80") (pin "1") (pinfunction "1_1") (pintype "passive"))
      (node (ref "C81") (pin "1") (pinfunction "1_1") (pintype "passive"))
      (node (ref "C82") (pin "1") (pinfunction "1_1") (pintype "passive"))
      (node (ref "C83") (pin "1") (pinfunction "1_1") (pintype "passive"))
      (node (ref "P40") (pin "2") (pinfunction "2_2") (pintype "passive"))
      (node (ref "P40") (pin "5") (pinfunction "5_5") (pintype "passive"))
      (node (ref "P41") (pin "16") (pinfunction "16_16") (pintype "passive"))
      (node (ref "P41") (pin "19") (pinfunction "19_19") (pintype "passive"))
      (node (ref "P42") (pin "2") (pinfunction "2_2") (pintype "passive"))
      (node (ref "P42") (pin "5") (pinfunction "5_5") (pintype "passive"))
      (node (ref "P43") (pin "16") (pinfunction "16_16") (pintype "passive"))
      (node (ref "P43") (pin "19") (pinfunction "19_19") (pintype "passive"))
      (node (ref "R40") (pin "2") (pinfunction "2_2") (pintype "passive"))
      (node (ref "R41") (pin "1") (pinfunction "1_1") (pintype "passive"))
      (node (ref "R47") (pin "1") (pinfunction "1_1") (pintype "passive"))
      (node (ref "R49") (pin "2") (pinfunction "2_2") (pintype "passive"))
      (node (ref "R53") (pin "1") (pinfunction "1_1") (pintype "passive"))
      (node (ref "R56") (pin "1") (pinfunction "1_1") (pintype "passive"))
      (node (ref "U40") (pin "2") (pinfunction "GND_2") (pintype "passive"))
      (node (ref "U40") (pin "5") (pinfunction "EPAD_5") (pintype "passive"))
      (node (ref "U41") (pin "10") (pinfunction "GND_10") (pintype "power_in"))
      (node (ref "U41") (pin "11") (pinfunction "GND_11") (pintype "power_in"))
      (node (ref "U42") (pin "2") (pinfunction "GND_2") (pintype "passive"))
      (node (ref "U42") (pin "5") (pinfunction "EPAD_5") (pintype "passive"))
      (node (ref "U43") (pin "2") (pinfunction "GND_2") (pintype "passive"))
      (node (ref "U43") (pin "5") (pinfunction "EPAD_5") (pintype "passive"))
      (node (ref "U44") (pin "10") (pinfunction "GND_10") (pintype "power_in"))
      (node (ref "U44") (pin "11") (pinfunction "GND_11") (pintype "power_in"))
      (node (ref "U45") (pin "2") (pinfunction "GND_2") (pintype "passive"))
      (node (ref "U45") (pin "5") (pinfunction "EPAD_5") (pintype "passive"))
      (node (ref "U46") (pin "2") (pinfunction "GND_2") (pintype "passive"))
      (node (ref "U46") (pin "5") (pinfunction "EPAD_5") (pintype "passive"))
      (node (ref "U47") (pin "10") (pinfunction "GND_10") (pintype "power_in"))
      (node (ref "U47") (pin "11") (pinfunction "GND_11") (pintype "power_in"))
      (node (ref "U48") (pin "2") (pinfunction "GND_2") (pintype "passive"))
      (node (ref "U48") (pin "5") (pinfunction "EPAD_5") (pintype "passive"))
      (node (ref "U49") (pin "10") (pinfunction "GND_10") (pintype "power_in"))
      (node (ref "U49") (pin "11") (pinfunction "GND_11") (pintype "power_in"))
    )
    (net (code "88") (name "Net-(P40-Pad7)") (class "Default")
      (node (ref "P40") (pin "7") (pinfunction "7_7") (pintype "passive"))
      (node (ref "P40") (pin "9") (pinfunction "9_9") (pintype "passive"))
      (node (ref "R42") (pin "1") (pinfunction "1_1") (pintype "passive"))
    )
    (net (code "89") (name "Net-(P40-Pad11)") (class "Default")
      (node (ref "P40") (pin "11") (pinfunction "11_11") (pintype "passive"))
      (node (ref "P40") (pin "13") (pinfunction "13_13") (pintype "passive"))
      (node (ref "P40") (pin "15") (pinfunction "15_15") (pintype "passive"))
      (node (ref "R43") (pin "1") (pinfunction "1_1") (pintype "passive"))
    )
    (net (code "90") (name "Net-(P40-Pad17)") (class "Default")
      (node (ref "P40") (pin "17") (pinfunction "17_17") (pintype "passive"))
      (node (ref "P40") (pin "19") (pinfunction "19_19") (pintype "passive"))
      (node (ref "R45") (pin "1") (pinfunction "1_1") (pintype "passive"))
    )
    (net (code "91") (name "Net-(P42-Pad7)") (class "Default")
      (node (ref "P42") (pin "7") (pinfunction "7_7") (pintype "passive"))
      (node (ref "P42") (pin "9") (pinfunction "9_9") (pintype "passive"))
      (node (ref "R50") (pin "1") (pinfunction "1_1") (pintype "passive"))
    )
    (net (code "92") (name "Net-(P42-Pad11)") (class "Default")
      (node (ref "P42") (pin "11") (pinfunction "11_11") (pintype "passive"))
      (node (ref "P42") (pin "13") (pinfunction "13_13") (pintype "passive"))
      (node (ref "P42") (pin "15") (pinfunction "15_15") (pintype "passive"))
      (node (ref "R51") (pin "1") (pinfunction "1_1") (pintype "passive"))
    )
    (net (code "93") (name "Net-(P42-Pad17)") (class "Default")
      (node (ref "P42") (pin "17") (pinfunction "17_17") (pintype "passive"))
      (node (ref "P42") (pin "19") (pinfunction "19_19") (pintype "passive"))
      (node (ref "R52") (pin "1") (pinfunction "1_1") (pintype "passive"))
    )
    (net (code "94") (name "Net-(U40-IN)") (class "Default")
      (node (ref "C40") (pin "2") (pinfunction "2_2") (pintype "passive"))
      (node (ref "C41") (pin "2") (pinfunction "2_2") (pintype "passive"))
      (node (ref "C42") (pin "2") (pinfunction "2_2") (pintype "passive"))
      (node (ref "L44") (pin "2") (pinfunction "2_2") (pintype "passive"))
      (node (ref "U40") (pin "4") (pinfunction "IN_4") (pintype "passive"))
    )
    (net (code "95") (name "Net-(U42-IN)") (class "Default")
      (node (ref "C48") (pin "2") (pinfunction "2_2") (pintype "passive"))
      (node (ref "C49") (pin "2") (pinfunction "2_2") (pintype "passive"))
      (node (ref "C50") (pin "2") (pinfunction "2_2") (pintype "passive"))
      (node (ref "L45") (pin "2") (pinfunction "2_2") (pintype "passive"))
      (node (ref "L46") (pin "2") (pinfunction "2_2") (pintype "passive"))
      (node (ref "U42") (pin "4") (pinfunction "IN_4") (pintype "passive"))
    )
    (net (code "96") (name "Net-(U43-IN)") (class "Default")
      (node (ref "C54") (pin "2") (pinfunction "2_2") (pintype "passive"))
      (node (ref "C55") (pin "2") (pinfunction "2_2") (pintype "passive"))
      (node (ref "C56") (pin "2") (pinfunction "2_2") (pintype "passive"))
      (node (ref "L47") (pin "2") (pinfunction "2_2") (pintype "passive"))
      (node (ref "L48") (pin "2") (pinfunction "2_2") (pintype "passive"))
      (node (ref "U43") (pin "4") (pinfunction "IN_4") (pintype "passive"))
    )
    (net (code "97") (name "Net-(U45-IN)") (class "Default")
      (node (ref "C62") (pin "2") (pinfunction "2_2") (pintype "passive"))
      (node (ref "C63") (pin "2") (pinfunction "2_2") (pintype "passive"))
      (node (ref "C64") (pin "2") (pinfunction "2_2") (pintype "passive"))
      (node (ref "L53") (pin "2") (pinfunction "2_2") (pintype "passive"))
      (node (ref "U45") (pin "4") (pinfunction "IN_4") (pintype "passive"))
    )
    (net (code "98") (name "Net-(U46-IN)") (class "Default")
      (node (ref "C68") (pin "2") (pinfunction "2_2") (pintype "passive"))
      (node (ref "C69") (pin "2") (pinfunction "2_2") (pintype "passive"))
      (node (ref "C70") (pin "2") (pinfunction "2_2") (pintype "passive"))
      (node (ref "L54") (pin "2") (pinfunction "2_2") (pintype "passive"))
      (node (ref "L55") (pin "2") (pinfunction "2_2") (pintype "passive"))
      (node (ref "U46") (pin "4") (pinfunction "IN_4") (pintype "passive"))
    )
    (net (code "99") (name "Net-(U48-IN)") (class "Default")
      (node (ref "C74") (pin "2") (pinfunction "2_2") (pintype "passive"))
      (node (ref "C75") (pin "2") (pinfunction "2_2") (pintype "passive"))
      (node (ref "C76") (pin "2") (pinfunction "2_2") (pintype "passive"))
      (node (ref "L56") (pin "2") (pinfunction "2_2") (pintype "passive"))
      (node (ref "L57") (pin "2") (pinfunction "2_2") (pintype "passive"))
      (node (ref "U48") (pin "4") (pinfunction "IN_4") (pintype "passive"))
    )
    (net (code "100") (name "unconnected-(P40-Pad20)") (class "Default")
      (node (ref "P40") (pin "20") (pinfunction "20_20") (pintype "passive"))
    )
    (net (code "101") (name "unconnected-(P41-Pad2)") (class "Default")
      (node (ref "P41") (pin "2") (pinfunction "2_2") (pintype "passive"))
    )
    (net (code "102") (name "unconnected-(P41-Pad4)") (class "Default")
      (node (ref "P41") (pin "4") (pinfunction "4_4") (pintype "passive"))
    )
    (net (code "103") (name "unconnected-(P41-Pad6)") (class "Default")
      (node (ref "P41") (pin "6") (pinfunction "6_6") (pintype "passive"))
    )
    (net (code "104") (name "unconnected-(P41-Pad8)") (class "Default")
      (node (ref "P41") (pin "8") (pinfunction "8_8") (pintype "passive"))
    )
    (net (code "105") (name "unconnected-(P41-Pad10)") (class "Default")
      (node (ref "P41") (pin "10") (pinfunction "10_10") (pintype "passive"))
    )
    (net (code "106") (name "unconnected-(P41-Pad12)") (class "Default")
      (node (ref "P41") (pin "12") (pinfunction "12_12") (pintype "passive"))
    )
    (net (code "107") (name "unconnected-(P41-Pad14)") (class "Default")
      (node (ref "P41") (pin "14") (pinfunction "14_14") (pintype "passive"))
    )
    (net (code "108") (name "unconnected-(P42-Pad20)") (class "Default")
      (node (ref "P42") (pin "20") (pinfunction "20_20") (pintype "passive"))
    )
    (net (code "109") (name "unconnected-(P43-Pad2)") (class "Default")
      (node (ref "P43") (pin "2") (pinfunction "2_2") (pintype "passive"))
    )
    (net (code "110") (name "unconnected-(P43-Pad4)") (class "Default")
      (node (ref "P43") (pin "4") (pinfunction "4_4") (pintype "passive"))
    )
    (net (code "111") (name "unconnected-(P43-Pad6)") (class "Default")
      (node (ref "P43") (pin "6") (pinfunction "6_6") (pintype "passive"))
    )
    (net (code "112") (name "unconnected-(P43-Pad8)") (class "Default")
      (node (ref "P43") (pin "8") (pinfunction "8_8") (pintype "passive"))
    )
    (net (code "113") (name "unconnected-(P43-Pad10)") (class "Default")
      (node (ref "P43") (pin "10") (pinfunction "10_10") (pintype "passive"))
    )
    (net (code "114") (name "unconnected-(P43-Pad12)") (class "Default")
      (node (ref "P43") (pin "12") (pinfunction "12_12") (pintype "passive"))
    )
    (net (code "115") (name "unconnected-(P43-Pad14)") (class "Default")
      (node (ref "P43") (pin "14") (pinfunction "14_14") (pintype "passive"))
    )
  )
)
